# Controller.net
KiCad netlist of a schematic drawn in Altium Designer
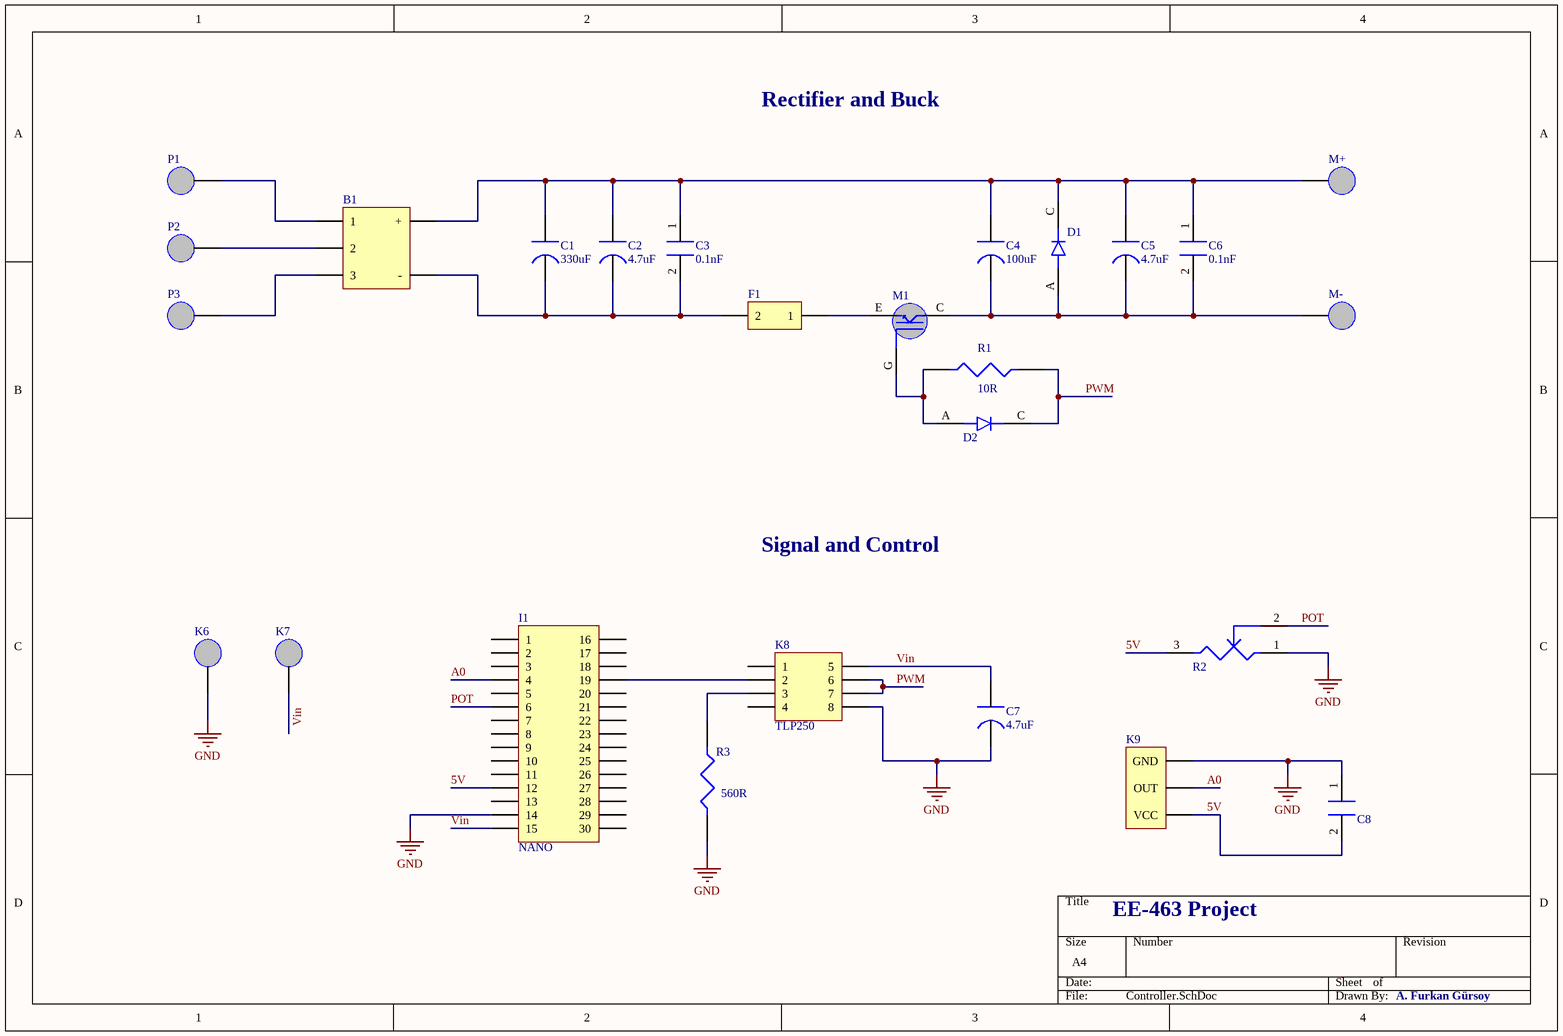
[diagram p0: Controller.SchDoc]

(export (version "E")
  (design (tool "Eeschema 10.0.6"))
  (components
    (comp (ref "B1") (value "B?") (footprint "36mt160") (libsource (lib "GetRektified") (part "36MT160")))
    (comp (ref "C1")
      (value "330uF")
      (footprint "330uF400V")
      (description "330uF400V")
      (libsource (lib "GetRektified") (part "330uF400V"))
    )
    (comp (ref "C2")
      (value "4.7uF")
      (footprint "4.7uF400V")
      (libsource (lib "GetRektified") (part "4.7uF400V"))
    )
    (comp (ref "C3")
      (value "0.1nF")
      (footprint "0.1nf1000V")
      (libsource (lib "GetRektified") (part "0.1nF1000V"))
    )
    (comp (ref "C4")
      (value "100uF")
      (footprint "100uF400V")
      (libsource (lib "GetRektified") (part "100uF400V"))
    )
    (comp (ref "C5")
      (value "4.7uF")
      (footprint "4.7uF400V")
      (libsource (lib "GetRektified") (part "4.7uF400V"))
    )
    (comp (ref "C6")
      (value "0.1nF")
      (footprint "0.1nf1000V")
      (libsource (lib "GetRektified") (part "0.1nF1000V"))
    )
    (comp (ref "C7")
      (value "4.7uF")
      (footprint "4.7uF400V")
      (libsource (lib "GetRektified") (part "4.7uF400V"))
    )
    (comp (ref "C8")
      (value "C8")
      (footprint "0.1nf1000V")
      (libsource (lib "GetRektified") (part "0.1nF1000V"))
    )
    (comp (ref "D1")
      (value "D?")
      (footprint "Heatsınk+Dıyot")
      (libsource (lib "GetRektified") (part "Heatsink+Diyot"))
    )
    (comp (ref "D2") (value "D2") (footprint "Diode-DIP") (libsource (lib "GetRektified") (part "Diyot")))
    (comp (ref "F1") (value "F?") (footprint "Sıgorta") (libsource (lib "GetRektified") (part "Sigorta")))
    (comp (ref "I1") (value "NANO") (footprint "Nano") (libsource (lib "GetRektified") (part "NANO")))
    (comp (ref "K6")
      (value "K6")
      (footprint "4mm Konnektor")
      (libsource (lib "GetRektified") (part "4mmKonnektor"))
    )
    (comp (ref "K7")
      (value "K7")
      (footprint "4mm Konnektor")
      (libsource (lib "GetRektified") (part "4mmKonnektor"))
    )
    (comp (ref "K8") (value "TLP250") (footprint "8DIP") (libsource (lib "GetRektified") (part "8DIPSoket")))
    (comp (ref "K9") (value "K?") (footprint "ACS") (libsource (lib "GetRektified") (part "ACS")))
    (comp (ref "M+")
      (value "K?")
      (footprint "4mm Konnektor")
      (libsource (lib "GetRektified") (part "4mmKonnektor"))
    )
    (comp (ref "M-")
      (value "K?")
      (footprint "4mm Konnektor")
      (libsource (lib "GetRektified") (part "4mmKonnektor"))
    )
    (comp (ref "M1")
      (value "M?")
      (footprint "Heatsink+IGBT")
      (libsource (lib "GetRektified") (part "Heatsink+IGBT"))
    )
    (comp (ref "P1")
      (value "K?")
      (footprint "4mm Konnektor")
      (libsource (lib "GetRektified") (part "4mmKonnektor"))
    )
    (comp (ref "P2")
      (value "K?")
      (footprint "4mm Konnektor")
      (libsource (lib "GetRektified") (part "4mmKonnektor"))
    )
    (comp (ref "P3")
      (value "K?")
      (footprint "4mm Konnektor")
      (libsource (lib "GetRektified") (part "4mmKonnektor"))
    )
    (comp (ref "R1") (value "10R") (footprint "10R") (libsource (lib "GetRektified") (part "10R")))
    (comp (ref "R2") (value "R2") (footprint "POT") (libsource (lib "GetRektified") (part "POT")))
    (comp (ref "R3") (value "560R") (footprint "10R") (libsource (lib "GetRektified") (part "10R")))
  )
  (nets
    (net (code "1") (name "/5V") (class "Default")
      (node (ref "C8") (pin "2") (pinfunction "2_2") (pintype "passive"))
      (node (ref "I1") (pin "12") (pinfunction "12_12") (pintype "passive"))
      (node (ref "K9") (pin "VCC") (pinfunction "VCC_VCC") (pintype "passive"))
      (node (ref "R2") (pin "3") (pinfunction "3_3") (pintype "passive"))
    )
    (net (code "2") (name "/A0") (class "Default")
      (node (ref "I1") (pin "4") (pinfunction "4_4") (pintype "passive"))
      (node (ref "K9") (pin "OUT") (pinfunction "OUT_OUT") (pintype "passive"))
    )
    (net (code "3") (name "/POT") (class "Default")
      (node (ref "I1") (pin "6") (pinfunction "6_6") (pintype "passive"))
      (node (ref "R2") (pin "2") (pinfunction "2_2") (pintype "passive"))
    )
    (net (code "4") (name "/PWM") (class "Default")
      (node (ref "D2") (pin "C") (pinfunction "31_C") (pintype "passive"))
      (node (ref "K8") (pin "6") (pinfunction "6_6") (pintype "passive"))
      (node (ref "K8") (pin "7") (pinfunction "7_7") (pintype "passive"))
      (node (ref "R1") (pin "1") (pinfunction "1_1") (pintype "passive"))
    )
    (net (code "5") (name "/Vin") (class "Default")
      (node (ref "C7") (pin "1") (pinfunction "1_1") (pintype "passive"))
      (node (ref "I1") (pin "15") (pinfunction "15_15") (pintype "passive"))
      (node (ref "K7") (pin "1") (pinfunction "1_1") (pintype "passive"))
      (node (ref "K8") (pin "5") (pinfunction "5_5") (pintype "passive"))
    )
    (net (code "6") (name "GND") (class "Default")
      (node (ref "C7") (pin "2") (pinfunction "2_2") (pintype "passive"))
      (node (ref "C8") (pin "1") (pinfunction "1_1") (pintype "passive"))
      (node (ref "I1") (pin "14") (pinfunction "14_14") (pintype "passive"))
      (node (ref "K6") (pin "1") (pinfunction "1_1") (pintype "passive"))
      (node (ref "K8") (pin "8") (pinfunction "8_8") (pintype "passive"))
      (node (ref "K9") (pin "GND") (pinfunction "GND_GND") (pintype "passive"))
      (node (ref "R2") (pin "1") (pinfunction "1_1") (pintype "passive"))
      (node (ref "R3") (pin "1") (pinfunction "1_1") (pintype "passive"))
    )
    (net (code "7") (name "Net-(B1-Pad-)") (class "Default")
      (node (ref "B1") (pin "-") (pinfunction "-_-") (pintype "passive"))
      (node (ref "C1") (pin "2") (pinfunction "2_2") (pintype "passive"))
      (node (ref "C2") (pin "2") (pinfunction "2_2") (pintype "passive"))
      (node (ref "C3") (pin "2") (pinfunction "2_2") (pintype "passive"))
      (node (ref "F1") (pin "2") (pinfunction "2_2") (pintype "passive"))
    )
    (net (code "8") (name "Net-(B1-Pad1)") (class "Default")
      (node (ref "B1") (pin "1") (pinfunction "1_1") (pintype "passive"))
      (node (ref "P1") (pin "1") (pinfunction "1_1") (pintype "passive"))
    )
    (net (code "9") (name "Net-(B1-Pad2)") (class "Default")
      (node (ref "B1") (pin "2") (pinfunction "2_2") (pintype "passive"))
      (node (ref "P2") (pin "1") (pinfunction "1_1") (pintype "passive"))
    )
    (net (code "10") (name "Net-(B1-Pad3)") (class "Default")
      (node (ref "B1") (pin "3") (pinfunction "3_3") (pintype "passive"))
      (node (ref "P3") (pin "1") (pinfunction "1_1") (pintype "passive"))
    )
    (net (code "11") (name "Net-(C4-Pad2)") (class "Default")
      (node (ref "C4") (pin "2") (pinfunction "2_2") (pintype "passive"))
      (node (ref "C5") (pin "2") (pinfunction "2_2") (pintype "passive"))
      (node (ref "C6") (pin "2") (pinfunction "2_2") (pintype "passive"))
      (node (ref "D1") (pin "A") (pinfunction "A_A") (pintype "passive"))
      (node (ref "M-") (pin "1") (pinfunction "1_1") (pintype "passive"))
      (node (ref "M1") (pin "C") (pinfunction "C_C") (pintype "passive"))
    )
    (net (code "12") (name "Net-(D1-31)") (class "Default")
      (node (ref "B1") (pin "+") (pinfunction "+_+") (pintype "passive"))
      (node (ref "C1") (pin "1") (pinfunction "1_1") (pintype "passive"))
      (node (ref "C2") (pin "1") (pinfunction "1_1") (pintype "passive"))
      (node (ref "C3") (pin "1") (pinfunction "1_1") (pintype "passive"))
      (node (ref "C4") (pin "1") (pinfunction "1_1") (pintype "passive"))
      (node (ref "C5") (pin "1") (pinfunction "1_1") (pintype "passive"))
      (node (ref "C6") (pin "1") (pinfunction "1_1") (pintype "passive"))
      (node (ref "D1") (pin "C") (pinfunction "31_C") (pintype "passive"))
      (node (ref "M+") (pin "1") (pinfunction "1_1") (pintype "passive"))
    )
    (net (code "13") (name "Net-(D2-PadA)") (class "Default")
      (node (ref "D2") (pin "A") (pinfunction "A_A") (pintype "passive"))
      (node (ref "M1") (pin "G") (pinfunction "G_G") (pintype "passive"))
      (node (ref "R1") (pin "2") (pinfunction "2_2") (pintype "passive"))
    )
    (net (code "14") (name "Net-(F1-Pad1)") (class "Default")
      (node (ref "F1") (pin "1") (pinfunction "1_1") (pintype "passive"))
      (node (ref "M1") (pin "E") (pinfunction "E_E") (pintype "passive"))
    )
    (net (code "15") (name "Net-(I1-Pad19)") (class "Default")
      (node (ref "I1") (pin "19") (pinfunction "19_19") (pintype "passive"))
      (node (ref "K8") (pin "2") (pinfunction "2_2") (pintype "passive"))
    )
    (net (code "16") (name "Net-(K8-Pad3)") (class "Default")
      (node (ref "K8") (pin "3") (pinfunction "3_3") (pintype "passive"))
      (node (ref "R3") (pin "2") (pinfunction "2_2") (pintype "passive"))
    )
    (net (code "17") (name "unconnected-(I1-Pad1)") (class "Default")
      (node (ref "I1") (pin "1") (pinfunction "1_1") (pintype "passive"))
    )
    (net (code "18") (name "unconnected-(I1-Pad2)") (class "Default")
      (node (ref "I1") (pin "2") (pinfunction "2_2") (pintype "passive"))
    )
    (net (code "19") (name "unconnected-(I1-Pad3)") (class "Default")
      (node (ref "I1") (pin "3") (pinfunction "3_3") (pintype "passive"))
    )
    (net (code "20") (name "unconnected-(I1-Pad5)") (class "Default")
      (node (ref "I1") (pin "5") (pinfunction "5_5") (pintype "passive"))
    )
    (net (code "21") (name "unconnected-(I1-Pad7)") (class "Default")
      (node (ref "I1") (pin "7") (pinfunction "7_7") (pintype "passive"))
    )
    (net (code "22") (name "unconnected-(I1-Pad8)") (class "Default")
      (node (ref "I1") (pin "8") (pinfunction "8_8") (pintype "passive"))
    )
    (net (code "23") (name "unconnected-(I1-Pad9)") (class "Default")
      (node (ref "I1") (pin "9") (pinfunction "9_9") (pintype "passive"))
    )
    (net (code "24") (name "unconnected-(I1-Pad10)") (class "Default")
      (node (ref "I1") (pin "10") (pinfunction "10_10") (pintype "passive"))
    )
    (net (code "25") (name "unconnected-(I1-Pad11)") (class "Default")
      (node (ref "I1") (pin "11") (pinfunction "11_11") (pintype "passive"))
    )
    (net (code "26") (name "unconnected-(I1-Pad13)") (class "Default")
      (node (ref "I1") (pin "13") (pinfunction "13_13") (pintype "passive"))
    )
    (net (code "27") (name "unconnected-(I1-Pad16)") (class "Default")
      (node (ref "I1") (pin "16") (pinfunction "16_16") (pintype "passive"))
    )
    (net (code "28") (name "unconnected-(I1-Pad17)") (class "Default")
      (node (ref "I1") (pin "17") (pinfunction "17_17") (pintype "passive"))
    )
    (net (code "29") (name "unconnected-(I1-Pad18)") (class "Default")
      (node (ref "I1") (pin "18") (pinfunction "18_18") (pintype "passive"))
    )
    (net (code "30") (name "unconnected-(I1-Pad20)") (class "Default")
      (node (ref "I1") (pin "20") (pinfunction "20_20") (pintype "passive"))
    )
    (net (code "31") (name "unconnected-(I1-Pad21)") (class "Default")
      (node (ref "I1") (pin "21") (pinfunction "21_21") (pintype "passive"))
    )
    (net (code "32") (name "unconnected-(I1-Pad22)") (class "Default")
      (node (ref "I1") (pin "22") (pinfunction "22_22") (pintype "passive"))
    )
    (net (code "33") (name "unconnected-(I1-Pad23)") (class "Default")
      (node (ref "I1") (pin "23") (pinfunction "23_23") (pintype "passive"))
    )
    (net (code "34") (name "unconnected-(I1-Pad24)") (class "Default")
      (node (ref "I1") (pin "24") (pinfunction "24_24") (pintype "passive"))
    )
    (net (code "35") (name "unconnected-(I1-Pad25)") (class "Default")
      (node (ref "I1") (pin "25") (pinfunction "25_25") (pintype "passive"))
    )
    (net (code "36") (name "unconnected-(I1-Pad26)") (class "Default")
      (node (ref "I1") (pin "26") (pinfunction "26_26") (pintype "passive"))
    )
    (net (code "37") (name "unconnected-(I1-Pad27)") (class "Default")
      (node (ref "I1") (pin "27") (pinfunction "27_27") (pintype "passive"))
    )
    (net (code "38") (name "unconnected-(I1-Pad28)") (class "Default")
      (node (ref "I1") (pin "28") (pinfunction "28_28") (pintype "passive"))
    )
    (net (code "39") (name "unconnected-(I1-Pad29)") (class "Default")
      (node (ref "I1") (pin "29") (pinfunction "29_29") (pintype "passive"))
    )
    (net (code "40") (name "unconnected-(I1-Pad30)") (class "Default")
      (node (ref "I1") (pin "30") (pinfunction "30_30") (pintype "passive"))
    )
    (net (code "41") (name "unconnected-(K8-Pad1)") (class "Default")
      (node (ref "K8") (pin "1") (pinfunction "1_1") (pintype "passive"))
    )
    (net (code "42") (name "unconnected-(K8-Pad4)") (class "Default")
      (node (ref "K8") (pin "4") (pinfunction "4_4") (pintype "passive"))
    )
  )
)
